# eeZee_big_tiny.net
KiCad netlist of a schematic drawn in EAGLE
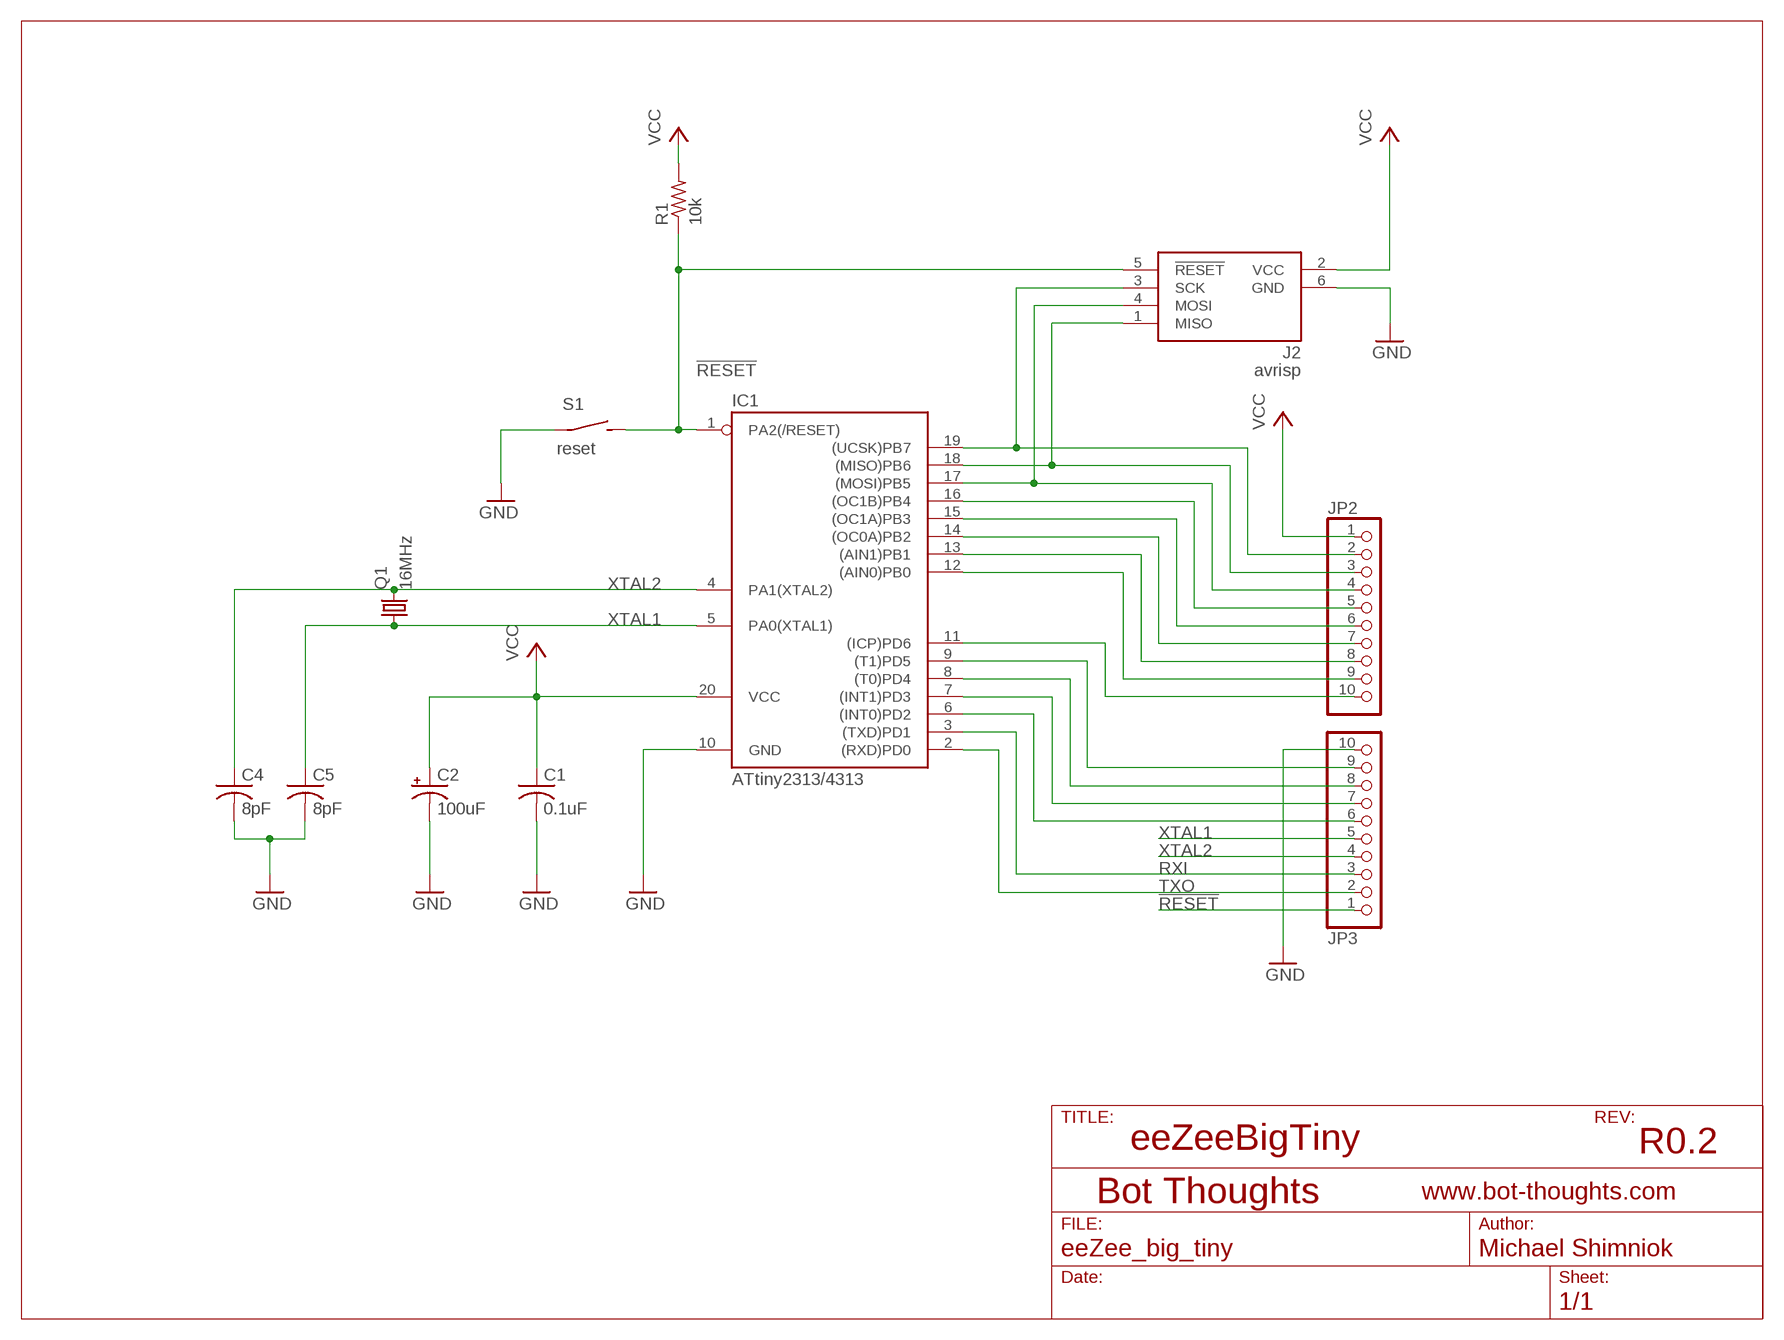
[diagram p0: schematic, sheet 1]

(export (version "E")
  (design (tool "Eeschema 10.0.6"))
  (components
    (comp (ref "C1")
      (value "0.1uF")
      (footprint "eagle-import:C0603")
      (fields (field (name "PARTNO") "0603YC104KAT2A"))
      (libsource (lib "eagle-import") (part "C-USC0603"))
    )
    (comp (ref "C2")
      (value "100uF")
      (footprint "eagle-import:SMC_B")
      (fields (field (name "PARTNO") "MCTT21X106M6R3CT"))
      (libsource (lib "eagle-import") (part "CPOL-USSMCB"))
    )
    (comp (ref "C4")
      (value "8pF")
      (footprint "eagle-import:C0603")
      (fields (field (name "PARTNO") "0603YC104KAT2A"))
      (libsource (lib "eagle-import") (part "C-USC0603"))
    )
    (comp (ref "C5")
      (value "8pF")
      (footprint "eagle-import:C0603")
      (fields (field (name "PARTNO") "0603YC104KAT2A"))
      (libsource (lib "eagle-import") (part "C-USC0603"))
    )
    (comp (ref "IC1")
      (value "ATtiny2313/4313")
      (footprint "eagle-import:DIL20")
      (libsource (lib "eagle-import") (part "TINY2313-P"))
    )
    (comp (ref "J2")
      (value "avrisp")
      (footprint "eagle-import:CON6P2R")
      (libsource (lib "eagle-import") (part "AVRISP6"))
    )
    (comp (ref "JP2")
      (value "PINHD-1X10_2.54-S")
      (footprint "eagle-import:1X10-S")
      (libsource (lib "eagle-import") (part "PINHD-1X10_2.54-S"))
    )
    (comp (ref "JP3")
      (value "PINHD-1X10_2.54-S")
      (footprint "eagle-import:1X10-S")
      (libsource (lib "eagle-import") (part "PINHD-1X10_2.54-S"))
    )
    (comp (ref "Q1")
      (value "16MHz")
      (footprint "eagle-import:NDK_2PAD_5X3")
      (libsource (lib "eagle-import") (part "CRYSTALNDK5X3"))
    )
    (comp (ref "R1")
      (value "10k")
      (footprint "eagle-import:R0603")
      (fields (field (name "PARTNO") "ERJ-3GEYJ103V"))
      (libsource (lib "eagle-import") (part "R-US_R0603"))
    )
    (comp (ref "S1")
      (value "reset")
      (footprint "eagle-import:6MMTACTILE_RECT")
      (libsource (lib "eagle-import") (part "SPST_TAC_RECT1"))
    )
  )
  (nets
    (net (code "1") (name "/RXI") (class "Default")
      (node (ref "IC1") (pin "3") (pinfunction "(TXD)PD1_3") (pintype "bidirectional"))
      (node (ref "JP3") (pin "3") (pinfunction "3_3") (pintype "passive"))
    )
    (net (code "2") (name "/TXO") (class "Default")
      (node (ref "IC1") (pin "2") (pinfunction "(RXD)PD0_2") (pintype "bidirectional"))
      (node (ref "JP3") (pin "2") (pinfunction "2_2") (pintype "passive"))
    )
    (net (code "3") (name "/XTAL1") (class "Default")
      (node (ref "C5") (pin "1") (pinfunction "1_1") (pintype "passive"))
      (node (ref "IC1") (pin "5") (pinfunction "PA0(XTAL1)_5") (pintype "bidirectional"))
      (node (ref "JP3") (pin "5") (pinfunction "5_5") (pintype "passive"))
      (node (ref "Q1") (pin "P$1") (pinfunction "1_P$1") (pintype "passive"))
    )
    (net (code "4") (name "/XTAL2") (class "Default")
      (node (ref "C4") (pin "1") (pinfunction "1_1") (pintype "passive"))
      (node (ref "IC1") (pin "4") (pinfunction "PA1(XTAL2)_4") (pintype "bidirectional"))
      (node (ref "JP3") (pin "4") (pinfunction "4_4") (pintype "passive"))
      (node (ref "Q1") (pin "P$2") (pinfunction "2_P$2") (pintype "passive"))
    )
    (net (code "5") (name "/~{RESET}") (class "Default")
      (node (ref "IC1") (pin "1") (pinfunction "PA2(/RESET)_1") (pintype "input"))
      (node (ref "J2") (pin "5") (pinfunction "~{RESET}_5") (pintype "output"))
      (node (ref "JP3") (pin "1") (pinfunction "1_1") (pintype "passive"))
      (node (ref "R1") (pin "1") (pinfunction "1_1") (pintype "passive"))
      (node (ref "S1") (pin "P$2") (pinfunction "S_P$2") (pintype "passive"))
    )
    (net (code "6") (name "GND") (class "Default")
      (node (ref "C1") (pin "2") (pinfunction "2_2") (pintype "passive"))
      (node (ref "C2") (pin "-") (pinfunction "-_-") (pintype "passive"))
      (node (ref "C4") (pin "2") (pinfunction "2_2") (pintype "passive"))
      (node (ref "C5") (pin "2") (pinfunction "2_2") (pintype "passive"))
      (node (ref "IC1") (pin "10") (pinfunction "GND_10") (pintype "power_in"))
      (node (ref "J2") (pin "6") (pinfunction "GND_6") (pintype "power_in"))
      (node (ref "JP3") (pin "10") (pinfunction "10_10") (pintype "passive"))
      (node (ref "S1") (pin "P$1") (pinfunction "P_P$1") (pintype "passive"))
    )
    (net (code "7") (name "Net-(IC1-(AIN0)PB0)") (class "Default")
      (node (ref "IC1") (pin "12") (pinfunction "(AIN0)PB0_12") (pintype "bidirectional"))
      (node (ref "JP2") (pin "9") (pinfunction "9_9") (pintype "passive"))
    )
    (net (code "8") (name "Net-(IC1-(AIN1)PB1)") (class "Default")
      (node (ref "IC1") (pin "13") (pinfunction "(AIN1)PB1_13") (pintype "bidirectional"))
      (node (ref "JP2") (pin "8") (pinfunction "8_8") (pintype "passive"))
    )
    (net (code "9") (name "Net-(IC1-(ICP)PD6)") (class "Default")
      (node (ref "IC1") (pin "11") (pinfunction "(ICP)PD6_11") (pintype "bidirectional"))
      (node (ref "JP2") (pin "10") (pinfunction "10_10") (pintype "passive"))
    )
    (net (code "10") (name "Net-(IC1-(INT0)PD2)") (class "Default")
      (node (ref "IC1") (pin "6") (pinfunction "(INT0)PD2_6") (pintype "bidirectional"))
      (node (ref "JP3") (pin "6") (pinfunction "6_6") (pintype "passive"))
    )
    (net (code "11") (name "Net-(IC1-(INT1)PD3)") (class "Default")
      (node (ref "IC1") (pin "7") (pinfunction "(INT1)PD3_7") (pintype "bidirectional"))
      (node (ref "JP3") (pin "7") (pinfunction "7_7") (pintype "passive"))
    )
    (net (code "12") (name "Net-(IC1-(MISO)PB6)") (class "Default")
      (node (ref "IC1") (pin "18") (pinfunction "(MISO)PB6_18") (pintype "bidirectional"))
      (node (ref "J2") (pin "1") (pinfunction "MISO_1") (pintype "input"))
      (node (ref "JP2") (pin "3") (pinfunction "3_3") (pintype "passive"))
    )
    (net (code "13") (name "Net-(IC1-(MOSI)PB5)") (class "Default")
      (node (ref "IC1") (pin "17") (pinfunction "(MOSI)PB5_17") (pintype "bidirectional"))
      (node (ref "J2") (pin "4") (pinfunction "MOSI_4") (pintype "output"))
      (node (ref "JP2") (pin "4") (pinfunction "4_4") (pintype "passive"))
    )
    (net (code "14") (name "Net-(IC1-(OC0A)PB2)") (class "Default")
      (node (ref "IC1") (pin "14") (pinfunction "(OC0A)PB2_14") (pintype "bidirectional"))
      (node (ref "JP2") (pin "7") (pinfunction "7_7") (pintype "passive"))
    )
    (net (code "15") (name "Net-(IC1-(OC1A)PB3)") (class "Default")
      (node (ref "IC1") (pin "15") (pinfunction "(OC1A)PB3_15") (pintype "bidirectional"))
      (node (ref "JP2") (pin "6") (pinfunction "6_6") (pintype "passive"))
    )
    (net (code "16") (name "Net-(IC1-(OC1B)PB4)") (class "Default")
      (node (ref "IC1") (pin "16") (pinfunction "(OC1B)PB4_16") (pintype "bidirectional"))
      (node (ref "JP2") (pin "5") (pinfunction "5_5") (pintype "passive"))
    )
    (net (code "17") (name "Net-(IC1-(T0)PD4)") (class "Default")
      (node (ref "IC1") (pin "8") (pinfunction "(T0)PD4_8") (pintype "bidirectional"))
      (node (ref "JP3") (pin "8") (pinfunction "8_8") (pintype "passive"))
    )
    (net (code "18") (name "Net-(IC1-(T1)PD5)") (class "Default")
      (node (ref "IC1") (pin "9") (pinfunction "(T1)PD5_9") (pintype "bidirectional"))
      (node (ref "JP3") (pin "9") (pinfunction "9_9") (pintype "passive"))
    )
    (net (code "19") (name "Net-(IC1-(UCSK)PB7)") (class "Default")
      (node (ref "IC1") (pin "19") (pinfunction "(UCSK)PB7_19") (pintype "bidirectional"))
      (node (ref "J2") (pin "3") (pinfunction "SCK_3") (pintype "output"))
      (node (ref "JP2") (pin "2") (pinfunction "2_2") (pintype "passive"))
    )
    (net (code "20") (name "VCC") (class "Default")
      (node (ref "C1") (pin "1") (pinfunction "1_1") (pintype "passive"))
      (node (ref "C2") (pin "+") (pinfunction "+_+") (pintype "passive"))
      (node (ref "IC1") (pin "20") (pinfunction "VCC_20") (pintype "power_in"))
      (node (ref "J2") (pin "2") (pinfunction "VCC_2") (pintype "power_in"))
      (node (ref "JP2") (pin "1") (pinfunction "1_1") (pintype "passive"))
      (node (ref "R1") (pin "2") (pinfunction "2_2") (pintype "passive"))
    )
  )
)
